# PCMCIA.net
KiCad netlist of a schematic drawn in Altium Designer
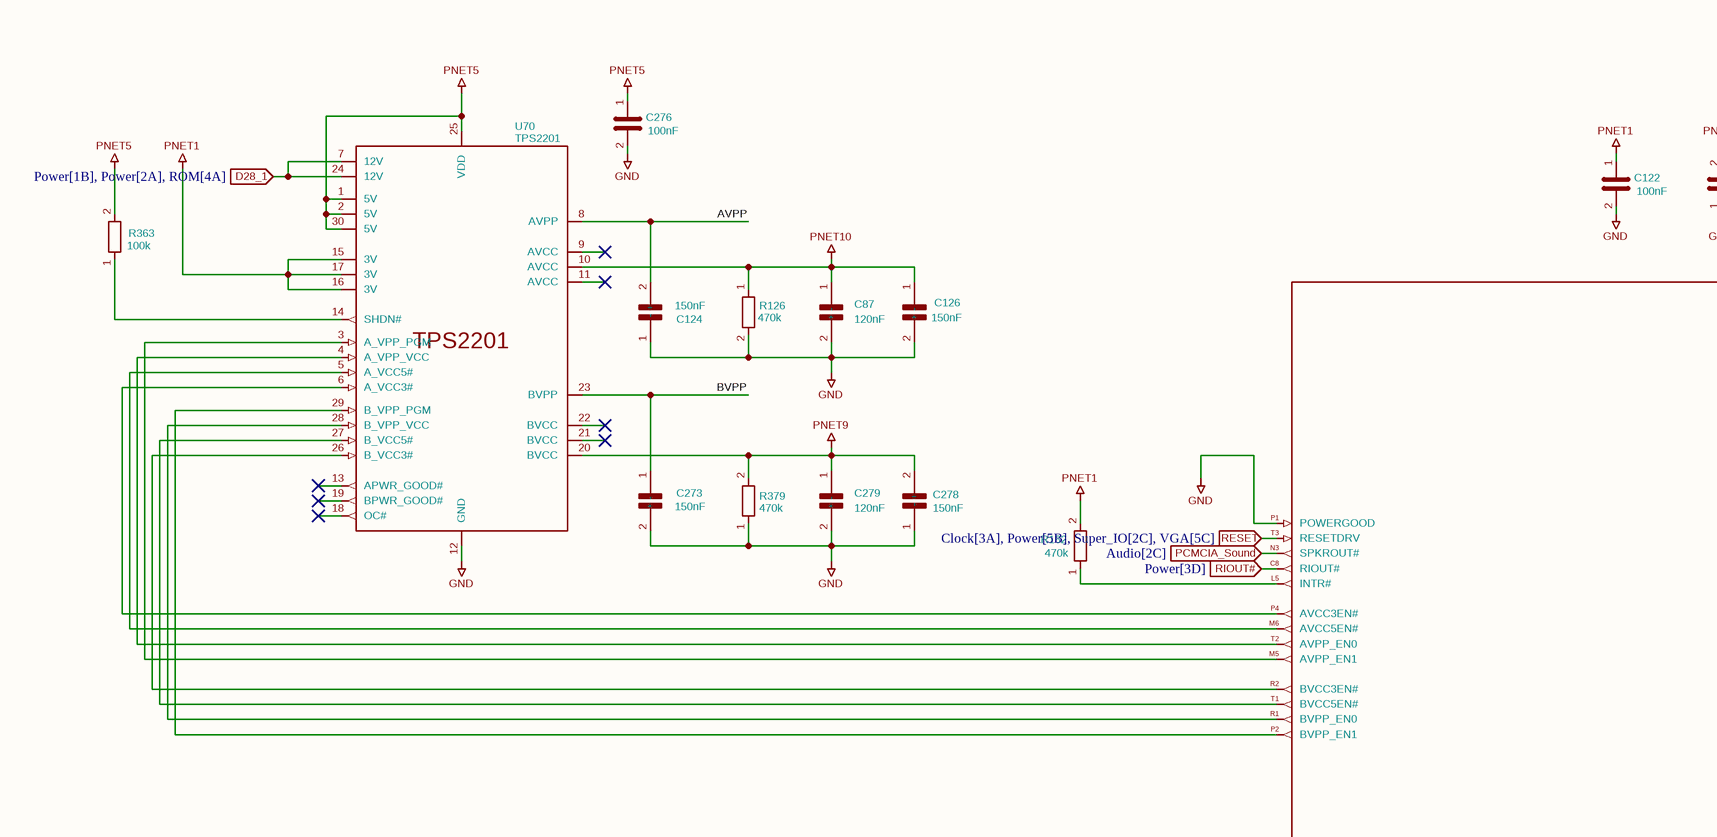
[diagram p0: PCMCIA.SchDoc, top left]
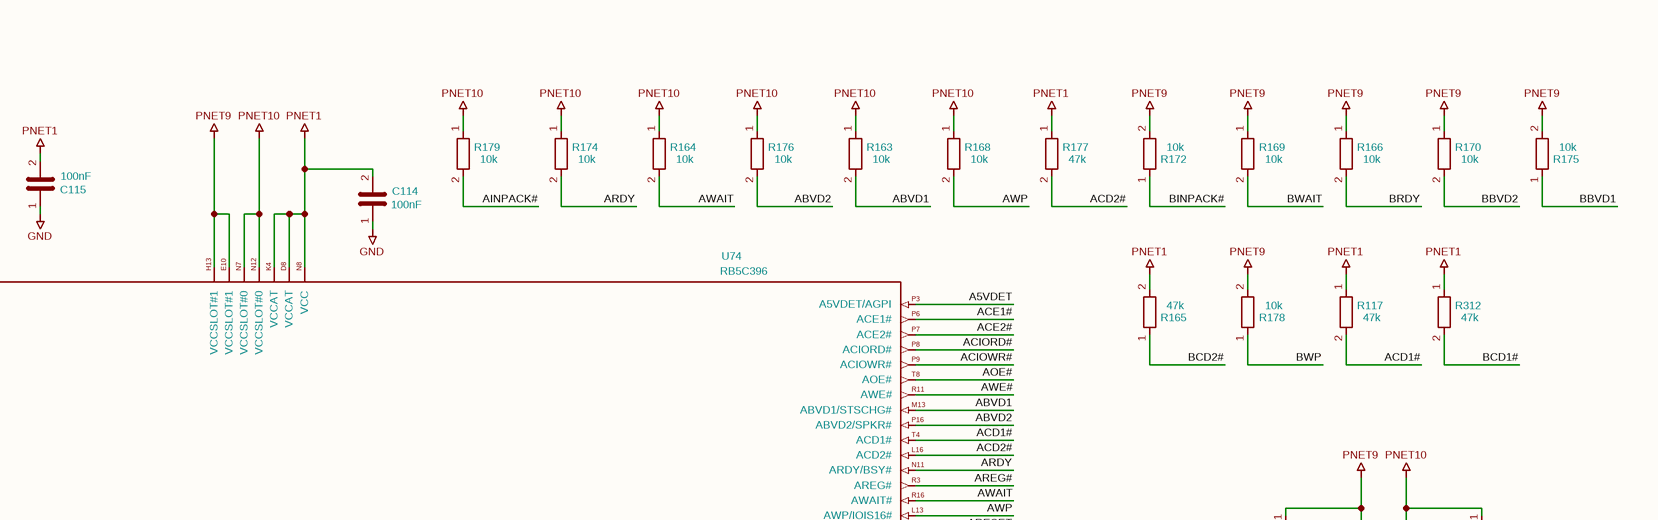
[diagram p1: PCMCIA.SchDoc, top right]
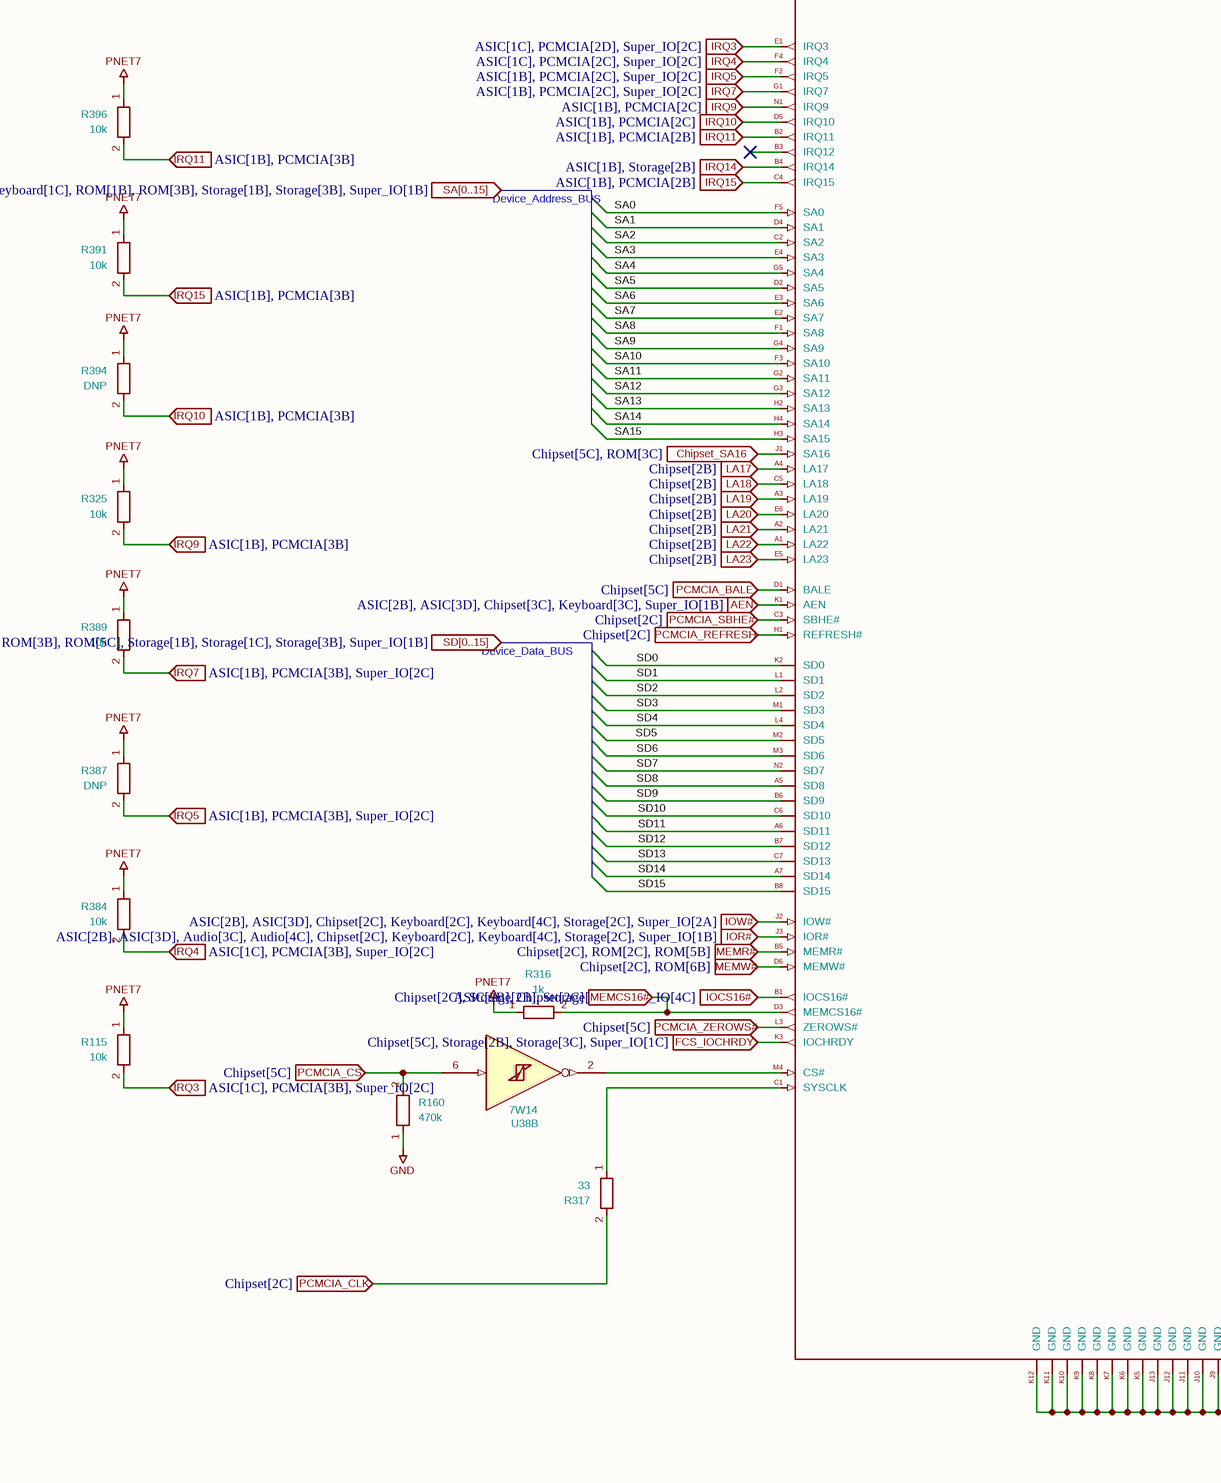
[diagram p2: PCMCIA.SchDoc, bottom left]
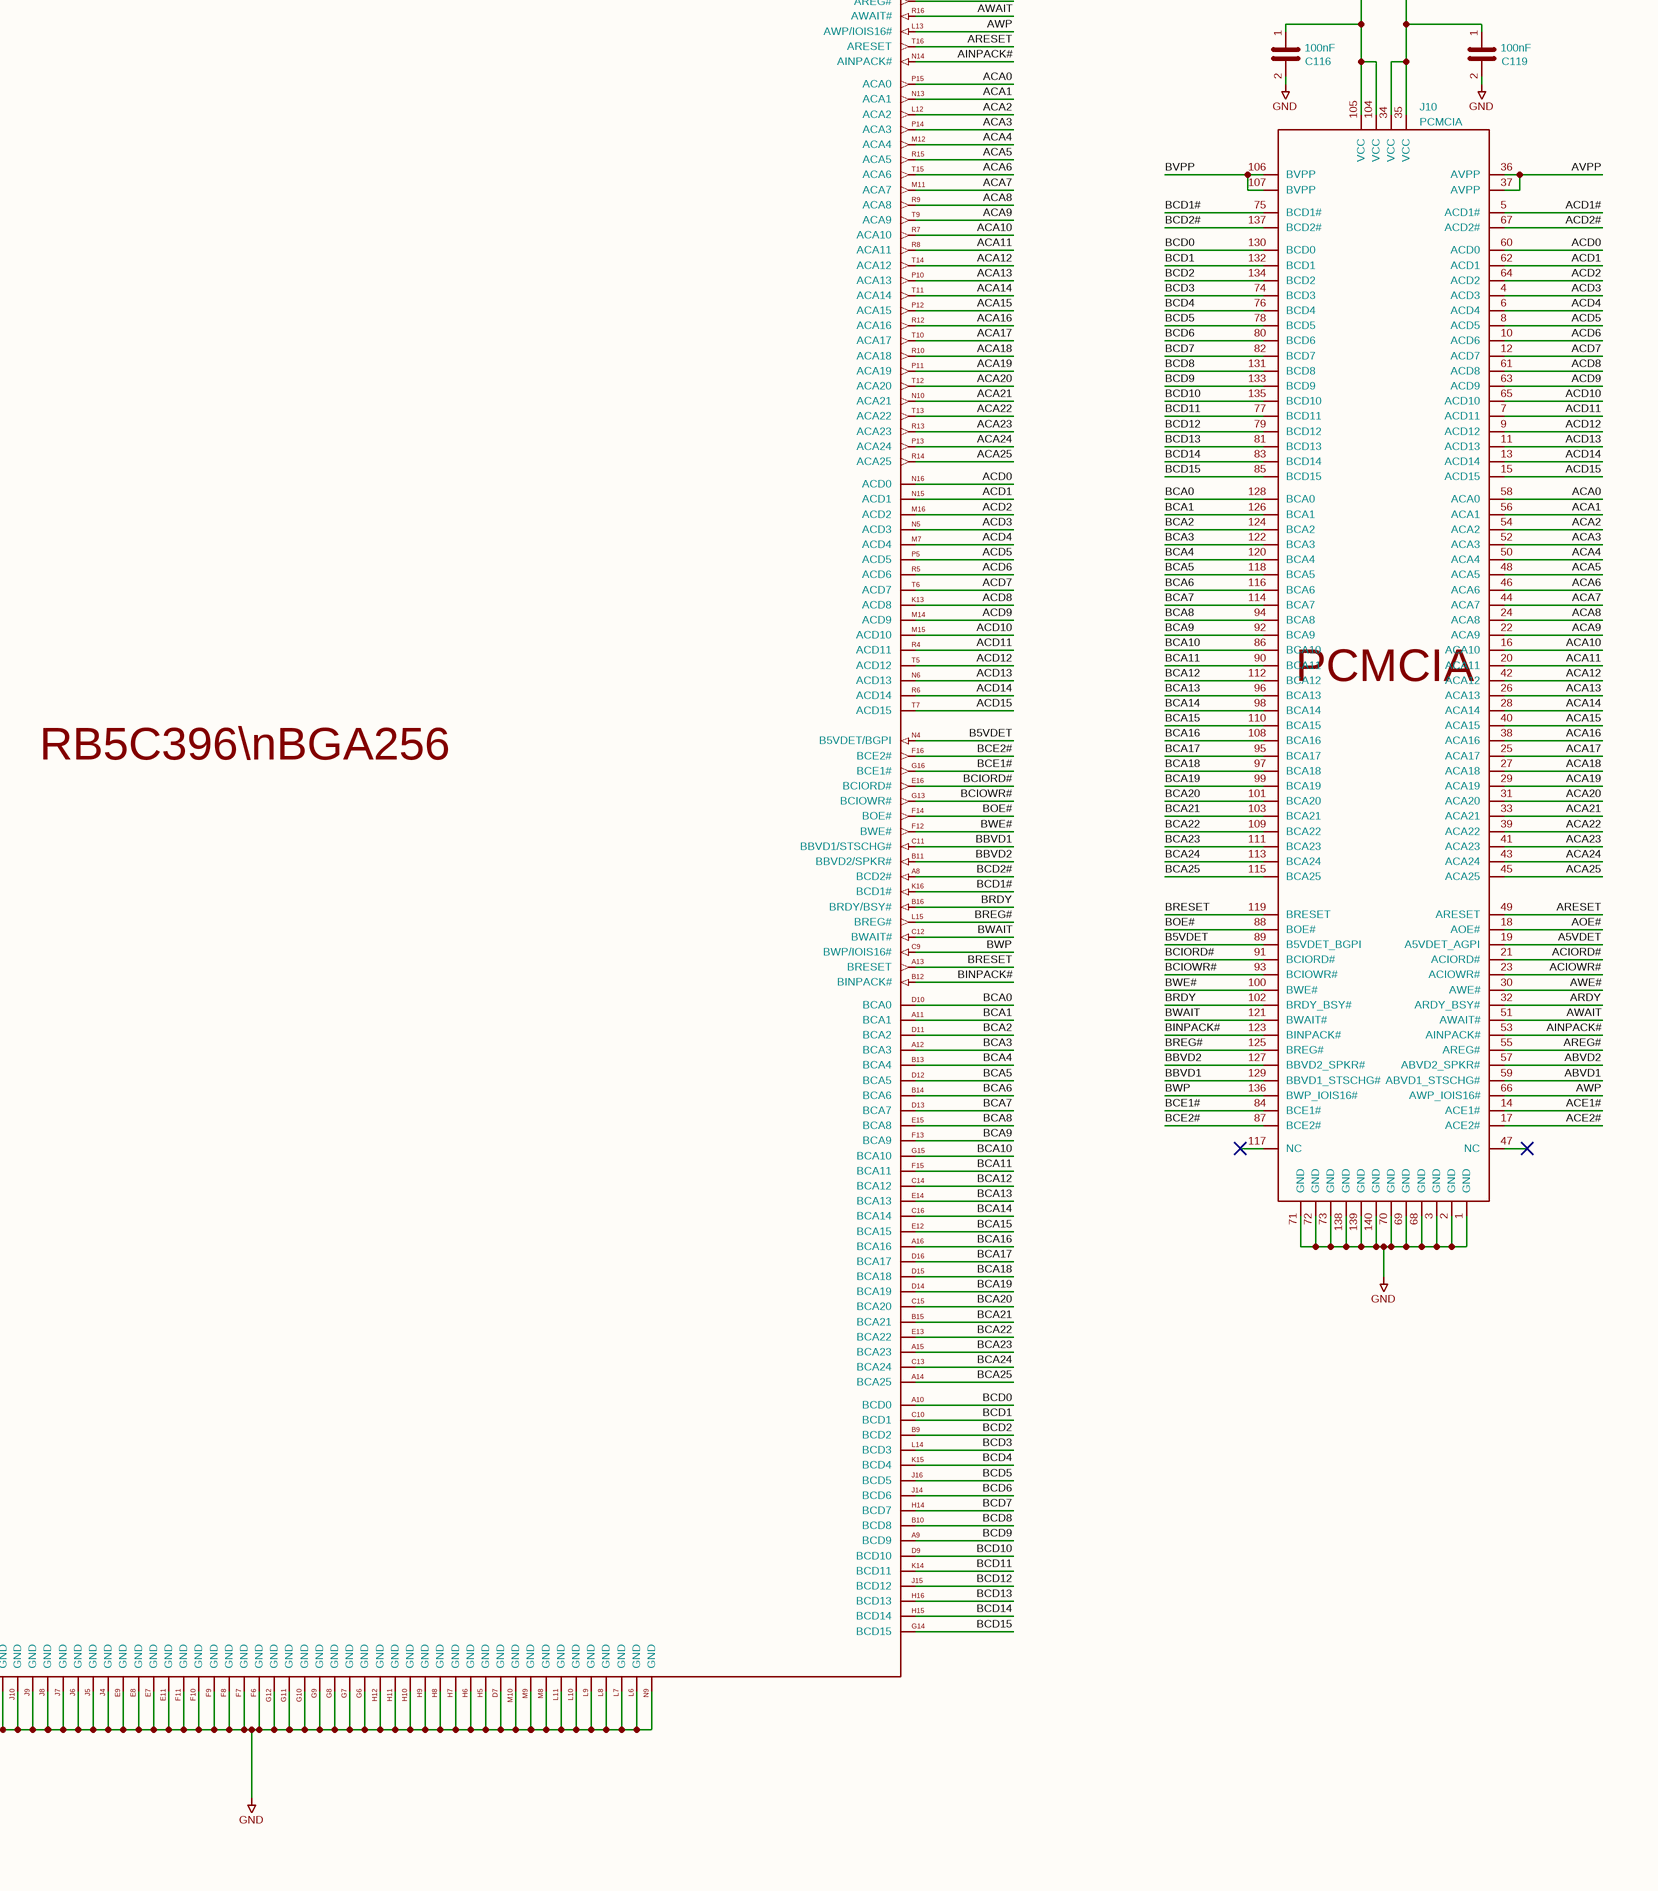
[diagram p3: PCMCIA.SchDoc, bottom right]

(export (version "E")
  (design (tool "Eeschema 10.0.6"))
  (components
    (comp (ref "C87")
      (value "120nF")
      (footprint "C_0402_1005Metric")
      (libsource (lib "PCM_Elektuur") (part "C"))
    )
    (comp (ref "C114") (value "100nF") (footprint "C_0402_1005Metric") (libsource (lib "Device") (part "C")))
    (comp (ref "C115") (value "100nF") (footprint "C_0402_1005Metric") (libsource (lib "Device") (part "C")))
    (comp (ref "C116") (value "100nF") (footprint "C_0402_1005Metric") (libsource (lib "Device") (part "C")))
    (comp (ref "C119") (value "100nF") (footprint "C_0402_1005Metric") (libsource (lib "Device") (part "C")))
    (comp (ref "C122") (value "100nF") (footprint "C_0402_1005Metric") (libsource (lib "Device") (part "C")))
    (comp (ref "C124") (value "150nF") (footprint "C_0603_1608Metric") (libsource (lib "") (part "C_1")))
    (comp (ref "C126")
      (value "150nF")
      (footprint "C_0402_1005Metric")
      (libsource (lib "PCM_Elektuur") (part "C"))
    )
    (comp (ref "C273")
      (value "150nF")
      (footprint "C_0603_1608Metric")
      (libsource (lib "PCM_Elektuur") (part "C"))
    )
    (comp (ref "C276") (value "100nF") (footprint "C_0402_1005Metric") (libsource (lib "Device") (part "C")))
    (comp (ref "C278") (value "150nF") (footprint "C_0402_1005Metric") (libsource (lib "") (part "C_1")))
    (comp (ref "C279")
      (value "120nF")
      (footprint "C_0402_1005Metric")
      (libsource (lib "PCM_Elektuur") (part "C"))
    )
    (comp (ref "J10") (value "PCMCIA") (footprint "PCMCIA") (libsource (lib "PC110") (part "PCMCIA_Conn")))
    (comp (ref "R115") (value "10k") (footprint "R_0402_1005Metric") (libsource (lib "Device") (part "R")))
    (comp (ref "R117") (value "47k") (footprint "R_0402_1005Metric") (libsource (lib "") (part "R_1")))
    (comp (ref "R126") (value "470k") (footprint "R_0402_1005Metric") (libsource (lib "") (part "R_1")))
    (comp (ref "R160") (value "470k") (footprint "R_0402_1005Metric") (libsource (lib "") (part "R_3")))
    (comp (ref "R162") (value "470k") (footprint "R_0402_1005Metric") (libsource (lib "") (part "R_3")))
    (comp (ref "R163") (value "10k") (footprint "R_0402_1005Metric") (libsource (lib "") (part "R_1")))
    (comp (ref "R164") (value "10k") (footprint "R_0402_1005Metric") (libsource (lib "") (part "R_1")))
    (comp (ref "R165") (value "47k") (footprint "R_0402_1005Metric") (libsource (lib "") (part "R_2")))
    (comp (ref "R166") (value "10k") (footprint "R_0402_1005Metric") (libsource (lib "") (part "R_1")))
    (comp (ref "R168") (value "10k") (footprint "R_0402_1005Metric") (libsource (lib "") (part "R_1")))
    (comp (ref "R169") (value "10k") (footprint "R_0402_1005Metric") (libsource (lib "") (part "R_1")))
    (comp (ref "R170") (value "10k") (footprint "R_0402_1005Metric") (libsource (lib "") (part "R_1")))
    (comp (ref "R172") (value "10k") (footprint "R_0402_1005Metric") (libsource (lib "") (part "R_2")))
    (comp (ref "R174") (value "10k") (footprint "R_0402_1005Metric") (libsource (lib "") (part "R_1")))
    (comp (ref "R175") (value "10k") (footprint "R_0402_1005Metric") (libsource (lib "") (part "R_2")))
    (comp (ref "R176") (value "10k") (footprint "R_0402_1005Metric") (libsource (lib "") (part "R_1")))
    (comp (ref "R177") (value "47k") (footprint "R_0402_1005Metric") (libsource (lib "") (part "R_1")))
    (comp (ref "R178") (value "10k") (footprint "R_0402_1005Metric") (libsource (lib "") (part "R_2")))
    (comp (ref "R179") (value "10k") (footprint "R_0402_1005Metric") (libsource (lib "") (part "R_1")))
    (comp (ref "R312") (value "47k") (footprint "R_0402_1005Metric") (libsource (lib "") (part "R_1")))
    (comp (ref "R316") (value "1k") (footprint "R_0402_1005Metric") (libsource (lib "") (part "R_2")))
    (comp (ref "R317") (value "33") (footprint "R_0402_1005Metric") (libsource (lib "") (part "R_1")))
    (comp (ref "R325") (value "10k") (footprint "R_0402_1005Metric") (libsource (lib "Device") (part "R")))
    (comp (ref "R363") (value "100k") (footprint "R_0402_1005Metric") (libsource (lib "") (part "R_2")))
    (comp (ref "R379") (value "470k") (footprint "R_0402_1005Metric") (libsource (lib "") (part "R_2")))
    (comp (ref "R384") (value "10k") (footprint "R_0402_1005Metric") (libsource (lib "Device") (part "R")))
    (comp (ref "R387") (value "DNP") (footprint "R_0402_1005Metric") (libsource (lib "Device") (part "R")))
    (comp (ref "R389") (value "10k") (footprint "R_0402_1005Metric") (libsource (lib "Device") (part "R")))
    (comp (ref "R391") (value "10k") (footprint "R_0402_1005Metric") (libsource (lib "Device") (part "R")))
    (comp (ref "R394") (value "DNP") (footprint "R_0402_1005Metric") (libsource (lib "Device") (part "R")))
    (comp (ref "R396") (value "10k") (footprint "R_0402_1005Metric") (libsource (lib "Device") (part "R")))
    (comp (ref "U38") (value "7W14") (footprint "sso-8") (libsource (lib "74xGxx") (part "74LVC3G14")))
    (comp (ref "U70")
      (value "TPS2201")
      (footprint "TSSOP-30_6.1x9.7mm_P0.65mm")
      (libsource (lib "PC110") (part "TPS2201"))
    )
    (comp (ref "U74") (value "RB5C396") (footprint "BGA-256") (libsource (lib "PC110") (part "RB5C396")))
  )
  (nets
    (net (code "1") (name "/A5VDET") (class "Default")
      (node (ref "J10") (pin "19") (pinfunction "A5VDET_AGPI_19") (pintype "bidirectional"))
      (node (ref "U74") (pin "P3") (pinfunction "A5VDET/AGPI_P3") (pintype "input"))
    )
    (net (code "2") (name "/ABVD1") (class "Default")
      (node (ref "J10") (pin "59") (pinfunction "ABVD1_STSCHG#_59") (pintype "bidirectional"))
      (node (ref "R163") (pin "2") (pinfunction "2_2") (pintype "passive"))
      (node (ref "U74") (pin "M13") (pinfunction "ABVD1/STSCHG#_M13") (pintype "input"))
    )
    (net (code "3") (name "/ABVD2") (class "Default")
      (node (ref "J10") (pin "57") (pinfunction "ABVD2_SPKR#_57") (pintype "bidirectional"))
      (node (ref "R176") (pin "2") (pinfunction "2_2") (pintype "passive"))
      (node (ref "U74") (pin "P16") (pinfunction "ABVD2/SPKR#_P16") (pintype "input"))
    )
    (net (code "4") (name "/ACA0") (class "Default")
      (node (ref "J10") (pin "58") (pinfunction "ACA0_58") (pintype "bidirectional"))
      (node (ref "U74") (pin "P15") (pinfunction "ACA0_P15") (pintype "output"))
    )
    (net (code "5") (name "/ACA1") (class "Default")
      (node (ref "J10") (pin "56") (pinfunction "ACA1_56") (pintype "bidirectional"))
      (node (ref "U74") (pin "N13") (pinfunction "ACA1_N13") (pintype "output"))
    )
    (net (code "6") (name "/ACA2") (class "Default")
      (node (ref "J10") (pin "54") (pinfunction "ACA2_54") (pintype "bidirectional"))
      (node (ref "U74") (pin "L12") (pinfunction "ACA2_L12") (pintype "output"))
    )
    (net (code "7") (name "/ACA3") (class "Default")
      (node (ref "J10") (pin "52") (pinfunction "ACA3_52") (pintype "bidirectional"))
      (node (ref "U74") (pin "P14") (pinfunction "ACA3_P14") (pintype "output"))
    )
    (net (code "8") (name "/ACA4") (class "Default")
      (node (ref "J10") (pin "50") (pinfunction "ACA4_50") (pintype "bidirectional"))
      (node (ref "U74") (pin "M12") (pinfunction "ACA4_M12") (pintype "output"))
    )
    (net (code "9") (name "/ACA5") (class "Default")
      (node (ref "J10") (pin "48") (pinfunction "ACA5_48") (pintype "bidirectional"))
      (node (ref "U74") (pin "R15") (pinfunction "ACA5_R15") (pintype "output"))
    )
    (net (code "10") (name "/ACA6") (class "Default")
      (node (ref "J10") (pin "46") (pinfunction "ACA6_46") (pintype "bidirectional"))
      (node (ref "U74") (pin "T15") (pinfunction "ACA6_T15") (pintype "output"))
    )
    (net (code "11") (name "/ACA7") (class "Default")
      (node (ref "J10") (pin "44") (pinfunction "ACA7_44") (pintype "bidirectional"))
      (node (ref "U74") (pin "M11") (pinfunction "ACA7_M11") (pintype "output"))
    )
    (net (code "12") (name "/ACA8") (class "Default")
      (node (ref "J10") (pin "24") (pinfunction "ACA8_24") (pintype "bidirectional"))
      (node (ref "U74") (pin "R9") (pinfunction "ACA8_R9") (pintype "output"))
    )
    (net (code "13") (name "/ACA9") (class "Default")
      (node (ref "J10") (pin "22") (pinfunction "ACA9_22") (pintype "bidirectional"))
      (node (ref "U74") (pin "T9") (pinfunction "ACA9_T9") (pintype "output"))
    )
    (net (code "14") (name "/ACA10") (class "Default")
      (node (ref "J10") (pin "16") (pinfunction "ACA10_16") (pintype "bidirectional"))
      (node (ref "U74") (pin "R7") (pinfunction "ACA10_R7") (pintype "output"))
    )
    (net (code "15") (name "/ACA11") (class "Default")
      (node (ref "J10") (pin "20") (pinfunction "ACA11_20") (pintype "bidirectional"))
      (node (ref "U74") (pin "R8") (pinfunction "ACA11_R8") (pintype "output"))
    )
    (net (code "16") (name "/ACA12") (class "Default")
      (node (ref "J10") (pin "42") (pinfunction "ACA12_42") (pintype "bidirectional"))
      (node (ref "U74") (pin "T14") (pinfunction "ACA12_T14") (pintype "output"))
    )
    (net (code "17") (name "/ACA13") (class "Default")
      (node (ref "J10") (pin "26") (pinfunction "ACA13_26") (pintype "bidirectional"))
      (node (ref "U74") (pin "P10") (pinfunction "ACA13_P10") (pintype "output"))
    )
    (net (code "18") (name "/ACA14") (class "Default")
      (node (ref "J10") (pin "28") (pinfunction "ACA14_28") (pintype "bidirectional"))
      (node (ref "U74") (pin "T11") (pinfunction "ACA14_T11") (pintype "output"))
    )
    (net (code "19") (name "/ACA15") (class "Default")
      (node (ref "J10") (pin "40") (pinfunction "ACA15_40") (pintype "bidirectional"))
      (node (ref "U74") (pin "P12") (pinfunction "ACA15_P12") (pintype "output"))
    )
    (net (code "20") (name "/ACA16") (class "Default")
      (node (ref "J10") (pin "38") (pinfunction "ACA16_38") (pintype "bidirectional"))
      (node (ref "U74") (pin "R12") (pinfunction "ACA16_R12") (pintype "output"))
    )
    (net (code "21") (name "/ACA17") (class "Default")
      (node (ref "J10") (pin "25") (pinfunction "ACA17_25") (pintype "bidirectional"))
      (node (ref "U74") (pin "T10") (pinfunction "ACA17_T10") (pintype "output"))
    )
    (net (code "22") (name "/ACA18") (class "Default")
      (node (ref "J10") (pin "27") (pinfunction "ACA18_27") (pintype "bidirectional"))
      (node (ref "U74") (pin "R10") (pinfunction "ACA18_R10") (pintype "output"))
    )
    (net (code "23") (name "/ACA19") (class "Default")
      (node (ref "J10") (pin "29") (pinfunction "ACA19_29") (pintype "bidirectional"))
      (node (ref "U74") (pin "P11") (pinfunction "ACA19_P11") (pintype "output"))
    )
    (net (code "24") (name "/ACA20") (class "Default")
      (node (ref "J10") (pin "31") (pinfunction "ACA20_31") (pintype "bidirectional"))
      (node (ref "U74") (pin "T12") (pinfunction "ACA20_T12") (pintype "output"))
    )
    (net (code "25") (name "/ACA21") (class "Default")
      (node (ref "J10") (pin "33") (pinfunction "ACA21_33") (pintype "bidirectional"))
      (node (ref "U74") (pin "N10") (pinfunction "ACA21_N10") (pintype "output"))
    )
    (net (code "26") (name "/ACA22") (class "Default")
      (node (ref "J10") (pin "39") (pinfunction "ACA22_39") (pintype "bidirectional"))
      (node (ref "U74") (pin "T13") (pinfunction "ACA22_T13") (pintype "output"))
    )
    (net (code "27") (name "/ACA23") (class "Default")
      (node (ref "J10") (pin "41") (pinfunction "ACA23_41") (pintype "bidirectional"))
      (node (ref "U74") (pin "R13") (pinfunction "ACA23_R13") (pintype "output"))
    )
    (net (code "28") (name "/ACA24") (class "Default")
      (node (ref "J10") (pin "43") (pinfunction "ACA24_43") (pintype "bidirectional"))
      (node (ref "U74") (pin "P13") (pinfunction "ACA24_P13") (pintype "output"))
    )
    (net (code "29") (name "/ACA25") (class "Default")
      (node (ref "J10") (pin "45") (pinfunction "ACA25_45") (pintype "bidirectional"))
      (node (ref "U74") (pin "R14") (pinfunction "ACA25_R14") (pintype "output"))
    )
    (net (code "30") (name "/ACD0") (class "Default")
      (node (ref "J10") (pin "60") (pinfunction "ACD0_60") (pintype "bidirectional"))
      (node (ref "U74") (pin "N16") (pinfunction "ACD0_N16") (pintype "bidirectional"))
    )
    (net (code "31") (name "/ACD1") (class "Default")
      (node (ref "J10") (pin "62") (pinfunction "ACD1_62") (pintype "bidirectional"))
      (node (ref "U74") (pin "N15") (pinfunction "ACD1_N15") (pintype "bidirectional"))
    )
    (net (code "32") (name "/ACD1#") (class "Default")
      (node (ref "J10") (pin "5") (pinfunction "ACD1#_5") (pintype "bidirectional"))
      (node (ref "R117") (pin "2") (pinfunction "2_2") (pintype "passive"))
      (node (ref "U74") (pin "T4") (pinfunction "ACD1#_T4") (pintype "input"))
    )
    (net (code "33") (name "/ACD2") (class "Default")
      (node (ref "J10") (pin "64") (pinfunction "ACD2_64") (pintype "bidirectional"))
      (node (ref "U74") (pin "M16") (pinfunction "ACD2_M16") (pintype "bidirectional"))
    )
    (net (code "34") (name "/ACD2#") (class "Default")
      (node (ref "J10") (pin "67") (pinfunction "ACD2#_67") (pintype "bidirectional"))
      (node (ref "R177") (pin "2") (pinfunction "2_2") (pintype "passive"))
      (node (ref "U74") (pin "L16") (pinfunction "ACD2#_L16") (pintype "input"))
    )
    (net (code "35") (name "/ACD3") (class "Default")
      (node (ref "J10") (pin "4") (pinfunction "ACD3_4") (pintype "bidirectional"))
      (node (ref "U74") (pin "N5") (pinfunction "ACD3_N5") (pintype "bidirectional"))
    )
    (net (code "36") (name "/ACD4") (class "Default")
      (node (ref "J10") (pin "6") (pinfunction "ACD4_6") (pintype "bidirectional"))
      (node (ref "U74") (pin "M7") (pinfunction "ACD4_M7") (pintype "bidirectional"))
    )
    (net (code "37") (name "/ACD5") (class "Default")
      (node (ref "J10") (pin "8") (pinfunction "ACD5_8") (pintype "bidirectional"))
      (node (ref "U74") (pin "P5") (pinfunction "ACD5_P5") (pintype "bidirectional"))
    )
    (net (code "38") (name "/ACD6") (class "Default")
      (node (ref "J10") (pin "10") (pinfunction "ACD6_10") (pintype "bidirectional"))
      (node (ref "U74") (pin "R5") (pinfunction "ACD6_R5") (pintype "bidirectional"))
    )
    (net (code "39") (name "/ACD7") (class "Default")
      (node (ref "J10") (pin "12") (pinfunction "ACD7_12") (pintype "bidirectional"))
      (node (ref "U74") (pin "T6") (pinfunction "ACD7_T6") (pintype "bidirectional"))
    )
    (net (code "40") (name "/ACD8") (class "Default")
      (node (ref "J10") (pin "61") (pinfunction "ACD8_61") (pintype "bidirectional"))
      (node (ref "U74") (pin "K13") (pinfunction "ACD8_K13") (pintype "bidirectional"))
    )
    (net (code "41") (name "/ACD9") (class "Default")
      (node (ref "J10") (pin "63") (pinfunction "ACD9_63") (pintype "bidirectional"))
      (node (ref "U74") (pin "M14") (pinfunction "ACD9_M14") (pintype "bidirectional"))
    )
    (net (code "42") (name "/ACD10") (class "Default")
      (node (ref "J10") (pin "65") (pinfunction "ACD10_65") (pintype "bidirectional"))
      (node (ref "U74") (pin "M15") (pinfunction "ACD10_M15") (pintype "bidirectional"))
    )
    (net (code "43") (name "/ACD11") (class "Default")
      (node (ref "J10") (pin "7") (pinfunction "ACD11_7") (pintype "bidirectional"))
      (node (ref "U74") (pin "R4") (pinfunction "ACD11_R4") (pintype "bidirectional"))
    )
    (net (code "44") (name "/ACD12") (class "Default")
      (node (ref "J10") (pin "9") (pinfunction "ACD12_9") (pintype "bidirectional"))
      (node (ref "U74") (pin "T5") (pinfunction "ACD12_T5") (pintype "bidirectional"))
    )
    (net (code "45") (name "/ACD13") (class "Default")
      (node (ref "J10") (pin "11") (pinfunction "ACD13_11") (pintype "bidirectional"))
      (node (ref "U74") (pin "N6") (pinfunction "ACD13_N6") (pintype "bidirectional"))
    )
    (net (code "46") (name "/ACD14") (class "Default")
      (node (ref "J10") (pin "13") (pinfunction "ACD14_13") (pintype "bidirectional"))
      (node (ref "U74") (pin "R6") (pinfunction "ACD14_R6") (pintype "bidirectional"))
    )
    (net (code "47") (name "/ACD15") (class "Default")
      (node (ref "J10") (pin "15") (pinfunction "ACD15_15") (pintype "bidirectional"))
      (node (ref "U74") (pin "T7") (pinfunction "ACD15_T7") (pintype "bidirectional"))
    )
    (net (code "48") (name "/ACE1#") (class "Default")
      (node (ref "J10") (pin "14") (pinfunction "ACE1#_14") (pintype "bidirectional"))
      (node (ref "U74") (pin "P6") (pinfunction "ACE1#_P6") (pintype "output"))
    )
    (net (code "49") (name "/ACE2#") (class "Default")
      (node (ref "J10") (pin "17") (pinfunction "ACE2#_17") (pintype "bidirectional"))
      (node (ref "U74") (pin "P7") (pinfunction "ACE2#_P7") (pintype "output"))
    )
    (net (code "50") (name "/ACIORD#") (class "Default")
      (node (ref "J10") (pin "21") (pinfunction "ACIORD#_21") (pintype "bidirectional"))
      (node (ref "U74") (pin "P8") (pinfunction "ACIORD#_P8") (pintype "output"))
    )
    (net (code "51") (name "/ACIOWR#") (class "Default")
      (node (ref "J10") (pin "23") (pinfunction "ACIOWR#_23") (pintype "bidirectional"))
      (node (ref "U74") (pin "P9") (pinfunction "ACIOWR#_P9") (pintype "output"))
    )
    (net (code "52") (name "/AEN") (class "Default")
      (node (ref "U74") (pin "K1") (pinfunction "AEN_K1") (pintype "input"))
    )
    (net (code "53") (name "/AINPACK#") (class "Default")
      (node (ref "J10") (pin "53") (pinfunction "AINPACK#_53") (pintype "bidirectional"))
      (node (ref "R179") (pin "2") (pinfunction "2_2") (pintype "passive"))
      (node (ref "U74") (pin "N14") (pinfunction "AINPACK#_N14") (pintype "input"))
    )
    (net (code "54") (name "/AOE#") (class "Default")
      (node (ref "J10") (pin "18") (pinfunction "AOE#_18") (pintype "bidirectional"))
      (node (ref "U74") (pin "T8") (pinfunction "AOE#_T8") (pintype "output"))
    )
    (net (code "55") (name "/ARDY") (class "Default")
      (node (ref "J10") (pin "32") (pinfunction "ARDY_BSY#_32") (pintype "bidirectional"))
      (node (ref "R174") (pin "2") (pinfunction "2_2") (pintype "passive"))
      (node (ref "U74") (pin "N11") (pinfunction "ARDY/BSY#_N11") (pintype "input"))
    )
    (net (code "56") (name "/AREG#") (class "Default")
      (node (ref "J10") (pin "55") (pinfunction "AREG#_55") (pintype "bidirectional"))
      (node (ref "U74") (pin "R3") (pinfunction "AREG#_R3") (pintype "output"))
    )
    (net (code "57") (name "/ARESET") (class "Default")
      (node (ref "J10") (pin "49") (pinfunction "ARESET_49") (pintype "bidirectional"))
      (node (ref "U74") (pin "T16") (pinfunction "ARESET_T16") (pintype "output"))
    )
    (net (code "58") (name "/AVPP") (class "Default")
      (node (ref "C124") (pin "2") (pinfunction "-_2") (pintype "passive"))
      (node (ref "J10") (pin "36") (pinfunction "AVPP_36") (pintype "power_in"))
      (node (ref "J10") (pin "37") (pinfunction "AVPP_37") (pintype "power_in"))
      (node (ref "U70") (pin "8") (pinfunction "AVPP_8") (pintype "power_in"))
    )
    (net (code "59") (name "/AWAIT") (class "Default")
      (node (ref "J10") (pin "51") (pinfunction "AWAIT#_51") (pintype "bidirectional"))
      (node (ref "R164") (pin "2") (pinfunction "2_2") (pintype "passive"))
      (node (ref "U74") (pin "R16") (pinfunction "AWAIT#_R16") (pintype "input"))
    )
    (net (code "60") (name "/AWE#") (class "Default")
      (node (ref "J10") (pin "30") (pinfunction "AWE#_30") (pintype "bidirectional"))
      (node (ref "U74") (pin "R11") (pinfunction "AWE#_R11") (pintype "output"))
    )
    (net (code "61") (name "/AWP") (class "Default")
      (node (ref "J10") (pin "66") (pinfunction "AWP_IOIS16#_66") (pintype "bidirectional"))
      (node (ref "R168") (pin "2") (pinfunction "2_2") (pintype "passive"))
      (node (ref "U74") (pin "L13") (pinfunction "AWP/IOIS16#_L13") (pintype "input"))
    )
    (net (code "62") (name "/B5VDET") (class "Default")
      (node (ref "J10") (pin "89") (pinfunction "B5VDET_BGPI_89") (pintype "bidirectional"))
      (node (ref "U74") (pin "N4") (pinfunction "B5VDET/BGPI_N4") (pintype "input"))
    )
    (net (code "63") (name "/BBVD1") (class "Default")
      (node (ref "J10") (pin "129") (pinfunction "BBVD1_STSCHG#_129") (pintype "bidirectional"))
      (node (ref "R175") (pin "1") (pinfunction "1_1") (pintype "passive"))
      (node (ref "U74") (pin "C11") (pinfunction "BBVD1/STSCHG#_C11") (pintype "input"))
    )
    (net (code "64") (name "/BBVD2") (class "Default")
      (node (ref "J10") (pin "127") (pinfunction "BBVD2_SPKR#_127") (pintype "bidirectional"))
      (node (ref "R170") (pin "2") (pinfunction "2_2") (pintype "passive"))
      (node (ref "U74") (pin "B11") (pinfunction "BBVD2/SPKR#_B11") (pintype "input"))
    )
    (net (code "65") (name "/BCA0") (class "Default")
      (node (ref "J10") (pin "128") (pinfunction "BCA0_128") (pintype "bidirectional"))
      (node (ref "U74") (pin "D10") (pinfunction "BCA0_D10") (pintype "bidirectional"))
    )
    (net (code "66") (name "/BCA1") (class "Default")
      (node (ref "J10") (pin "126") (pinfunction "BCA1_126") (pintype "bidirectional"))
      (node (ref "U74") (pin "A11") (pinfunction "BCA1_A11") (pintype "bidirectional"))
    )
    (net (code "67") (name "/BCA2") (class "Default")
      (node (ref "J10") (pin "124") (pinfunction "BCA2_124") (pintype "bidirectional"))
      (node (ref "U74") (pin "D11") (pinfunction "BCA2_D11") (pintype "bidirectional"))
    )
    (net (code "68") (name "/BCA3") (class "Default")
      (node (ref "J10") (pin "122") (pinfunction "BCA3_122") (pintype "bidirectional"))
      (node (ref "U74") (pin "A12") (pinfunction "BCA3_A12") (pintype "bidirectional"))
    )
    (net (code "69") (name "/BCA4") (class "Default")
      (node (ref "J10") (pin "120") (pinfunction "BCA4_120") (pintype "bidirectional"))
      (node (ref "U74") (pin "B13") (pinfunction "BCA4_B13") (pintype "bidirectional"))
    )
    (net (code "70") (name "/BCA5") (class "Default")
      (node (ref "J10") (pin "118") (pinfunction "BCA5_118") (pintype "bidirectional"))
      (node (ref "U74") (pin "D12") (pinfunction "BCA5_D12") (pintype "bidirectional"))
    )
    (net (code "71") (name "/BCA6") (class "Default")
      (node (ref "J10") (pin "116") (pinfunction "BCA6_116") (pintype "bidirectional"))
      (node (ref "U74") (pin "B14") (pinfunction "BCA6_B14") (pintype "bidirectional"))
    )
    (net (code "72") (name "/BCA7") (class "Default")
      (node (ref "J10") (pin "114") (pinfunction "BCA7_114") (pintype "bidirectional"))
      (node (ref "U74") (pin "D13") (pinfunction "BCA7_D13") (pintype "bidirectional"))
    )
    (net (code "73") (name "/BCA8") (class "Default")
      (node (ref "J10") (pin "94") (pinfunction "BCA8_94") (pintype "bidirectional"))
      (node (ref "U74") (pin "E15") (pinfunction "BCA8_E15") (pintype "bidirectional"))
    )
    (net (code "74") (name "/BCA9") (class "Default")
      (node (ref "J10") (pin "92") (pinfunction "BCA9_92") (pintype "bidirectional"))
      (node (ref "U74") (pin "F13") (pinfunction "BCA9_F13") (pintype "bidirectional"))
    )
    (net (code "75") (name "/BCA10") (class "Default")
      (node (ref "J10") (pin "86") (pinfunction "BCA10_86") (pintype "bidirectional"))
      (node (ref "U74") (pin "G15") (pinfunction "BCA10_G15") (pintype "bidirectional"))
    )
    (net (code "76") (name "/BCA11") (class "Default")
      (node (ref "J10") (pin "90") (pinfunction "BCA11_90") (pintype "bidirectional"))
      (node (ref "U74") (pin "F15") (pinfunction "BCA11_F15") (pintype "bidirectional"))
    )
    (net (code "77") (name "/BCA12") (class "Default")
      (node (ref "J10") (pin "112") (pinfunction "BCA12_112") (pintype "bidirectional"))
      (node (ref "U74") (pin "C14") (pinfunction "BCA12_C14") (pintype "bidirectional"))
    )
    (net (code "78") (name "/BCA13") (class "Default")
      (node (ref "J10") (pin "96") (pinfunction "BCA13_96") (pintype "bidirectional"))
      (node (ref "U74") (pin "E14") (pinfunction "BCA13_E14") (pintype "bidirectional"))
    )
    (net (code "79") (name "/BCA14") (class "Default")
      (node (ref "J10") (pin "98") (pinfunction "BCA14_98") (pintype "bidirectional"))
      (node (ref "U74") (pin "C16") (pinfunction "BCA14_C16") (pintype "bidirectional"))
    )
    (net (code "80") (name "/BCA15") (class "Default")
      (node (ref "J10") (pin "110") (pinfunction "BCA15_110") (pintype "bidirectional"))
      (node (ref "U74") (pin "E12") (pinfunction "BCA15_E12") (pintype "bidirectional"))
    )
    (net (code "81") (name "/BCA16") (class "Default")
      (node (ref "J10") (pin "108") (pinfunction "BCA16_108") (pintype "bidirectional"))
      (node (ref "U74") (pin "A16") (pinfunction "BCA16_A16") (pintype "bidirectional"))
    )
    (net (code "82") (name "/BCA17") (class "Default")
      (node (ref "J10") (pin "95") (pinfunction "BCA17_95") (pintype "bidirectional"))
      (node (ref "U74") (pin "D16") (pinfunction "BCA17_D16") (pintype "bidirectional"))
    )
    (net (code "83") (name "/BCA18") (class "Default")
      (node (ref "J10") (pin "97") (pinfunction "BCA18_97") (pintype "bidirectional"))
      (node (ref "U74") (pin "D15") (pinfunction "BCA18_D15") (pintype "bidirectional"))
    )
    (net (code "84") (name "/BCA19") (class "Default")
      (node (ref "J10") (pin "99") (pinfunction "BCA19_99") (pintype "bidirectional"))
      (node (ref "U74") (pin "D14") (pinfunction "BCA19_D14") (pintype "bidirectional"))
    )
    (net (code "85") (name "/BCA20") (class "Default")
      (node (ref "J10") (pin "101") (pinfunction "BCA20_101") (pintype "bidirectional"))
      (node (ref "U74") (pin "C15") (pinfunction "BCA20_C15") (pintype "bidirectional"))
    )
    (net (code "86") (name "/BCA21") (class "Default")
      (node (ref "J10") (pin "103") (pinfunction "BCA21_103") (pintype "bidirectional"))
      (node (ref "U74") (pin "B15") (pinfunction "BCA21_B15") (pintype "bidirectional"))
    )
    (net (code "87") (name "/BCA22") (class "Default")
      (node (ref "J10") (pin "109") (pinfunction "BCA22_109") (pintype "bidirectional"))
      (node (ref "U74") (pin "E13") (pinfunction "BCA22_E13") (pintype "bidirectional"))
    )
    (net (code "88") (name "/BCA23") (class "Default")
      (node (ref "J10") (pin "111") (pinfunction "BCA23_111") (pintype "bidirectional"))
      (node (ref "U74") (pin "A15") (pinfunction "BCA23_A15") (pintype "bidirectional"))
    )
    (net (code "89") (name "/BCA24") (class "Default")
      (node (ref "J10") (pin "113") (pinfunction "BCA24_113") (pintype "bidirectional"))
      (node (ref "U74") (pin "C13") (pinfunction "BCA24_C13") (pintype "bidirectional"))
    )
    (net (code "90") (name "/BCA25") (class "Default")
      (node (ref "J10") (pin "115") (pinfunction "BCA25_115") (pintype "bidirectional"))
      (node (ref "U74") (pin "A14") (pinfunction "BCA25_A14") (pintype "bidirectional"))
    )
    (net (code "91") (name "/BCD0") (class "Default")
      (node (ref "J10") (pin "130") (pinfunction "BCD0_130") (pintype "bidirectional"))
      (node (ref "U74") (pin "A10") (pinfunction "BCD0_A10") (pintype "bidirectional"))
    )
    (net (code "92") (name "/BCD1") (class "Default")
      (node (ref "J10") (pin "132") (pinfunction "BCD1_132") (pintype "bidirectional"))
      (node (ref "U74") (pin "C10") (pinfunction "BCD1_C10") (pintype "bidirectional"))
    )
    (net (code "93") (name "/BCD1#") (class "Default")
      (node (ref "J10") (pin "75") (pinfunction "BCD1#_75") (pintype "bidirectional"))
      (node (ref "R312") (pin "2") (pinfunction "2_2") (pintype "passive"))
      (node (ref "U74") (pin "K16") (pinfunction "BCD1#_K16") (pintype "input"))
    )
    (net (code "94") (name "/BCD2") (class "Default")
      (node (ref "J10") (pin "134") (pinfunction "BCD2_134") (pintype "bidirectional"))
      (node (ref "U74") (pin "B9") (pinfunction "BCD2_B9") (pintype "bidirectional"))
    )
    (net (code "95") (name "/BCD2#") (class "Default")
      (node (ref "J10") (pin "137") (pinfunction "BCD2#_137") (pintype "bidirectional"))
      (node (ref "R165") (pin "1") (pinfunction "1_1") (pintype "passive"))
      (node (ref "U74") (pin "A8") (pinfunction "BCD2#_A8") (pintype "input"))
    )
    (net (code "96") (name "/BCD3") (class "Default")
      (node (ref "J10") (pin "74") (pinfunction "BCD3_74") (pintype "bidirectional"))
      (node (ref "U74") (pin "L14") (pinfunction "BCD3_L14") (pintype "bidirectional"))
    )
    (net (code "97") (name "/BCD4") (class "Default")
      (node (ref "J10") (pin "76") (pinfunction "BCD4_76") (pintype "bidirectional"))
      (node (ref "U74") (pin "K15") (pinfunction "BCD4_K15") (pintype "bidirectional"))
    )
    (net (code "98") (name "/BCD5") (class "Default")
      (node (ref "J10") (pin "78") (pinfunction "BCD5_78") (pintype "bidirectional"))
      (node (ref "U74") (pin "J16") (pinfunction "BCD5_J16") (pintype "bidirectional"))
    )
    (net (code "99") (name "/BCD6") (class "Default")
      (node (ref "J10") (pin "80") (pinfunction "BCD6_80") (pintype "bidirectional"))
      (node (ref "U74") (pin "J14") (pinfunction "BCD6_J14") (pintype "bidirectional"))
    )
    (net (code "100") (name "/BCD7") (class "Default")
      (node (ref "J10") (pin "82") (pinfunction "BCD7_82") (pintype "bidirectional"))
      (node (ref "U74") (pin "H14") (pinfunction "BCD7_H14") (pintype "bidirectional"))
    )
    (net (code "101") (name "/BCD8") (class "Default")
      (node (ref "J10") (pin "131") (pinfunction "BCD8_131") (pintype "bidirectional"))
      (node (ref "U74") (pin "B10") (pinfunction "BCD8_B10") (pintype "bidirectional"))
    )
    (net (code "102") (name "/BCD9") (class "Default")
      (node (ref "J10") (pin "133") (pinfunction "BCD9_133") (pintype "bidirectional"))
      (node (ref "U74") (pin "A9") (pinfunction "BCD9_A9") (pintype "bidirectional"))
    )
    (net (code "103") (name "/BCD10") (class "Default")
      (node (ref "J10") (pin "135") (pinfunction "BCD10_135") (pintype "bidirectional"))
      (node (ref "U74") (pin "D9") (pinfunction "BCD10_D9") (pintype "bidirectional"))
    )
    (net (code "104") (name "/BCD11") (class "Default")
      (node (ref "J10") (pin "77") (pinfunction "BCD11_77") (pintype "bidirectional"))
      (node (ref "U74") (pin "K14") (pinfunction "BCD11_K14") (pintype "bidirectional"))
    )
    (net (code "105") (name "/BCD12") (class "Default")
      (node (ref "J10") (pin "79") (pinfunction "BCD12_79") (pintype "bidirectional"))
      (node (ref "U74") (pin "J15") (pinfunction "BCD12_J15") (pintype "bidirectional"))
    )
    (net (code "106") (name "/BCD13") (class "Default")
      (node (ref "J10") (pin "81") (pinfunction "BCD13_81") (pintype "bidirectional"))
      (node (ref "U74") (pin "H16") (pinfunction "BCD13_H16") (pintype "bidirectional"))
    )
    (net (code "107") (name "/BCD14") (class "Default")
      (node (ref "J10") (pin "83") (pinfunction "BCD14_83") (pintype "bidirectional"))
      (node (ref "U74") (pin "H15") (pinfunction "BCD14_H15") (pintype "bidirectional"))
    )
    (net (code "108") (name "/BCD15") (class "Default")
      (node (ref "J10") (pin "85") (pinfunction "BCD15_85") (pintype "bidirectional"))
      (node (ref "U74") (pin "G14") (pinfunction "BCD15_G14") (pintype "bidirectional"))
    )
    (net (code "109") (name "/BCE1#") (class "Default")
      (node (ref "J10") (pin "84") (pinfunction "BCE1#_84") (pintype "bidirectional"))
      (node (ref "U74") (pin "G16") (pinfunction "BCE1#_G16") (pintype "output"))
    )
    (net (code "110") (name "/BCE2#") (class "Default")
      (node (ref "J10") (pin "87") (pinfunction "BCE2#_87") (pintype "bidirectional"))
      (node (ref "U74") (pin "F16") (pinfunction "BCE2#_F16") (pintype "output"))
    )
    (net (code "111") (name "/BCIORD#") (class "Default")
      (node (ref "J10") (pin "91") (pinfunction "BCIORD#_91") (pintype "bidirectional"))
      (node (ref "U74") (pin "E16") (pinfunction "BCIORD#_E16") (pintype "output"))
    )
    (net (code "112") (name "/BCIOWR#") (class "Default")
      (node (ref "J10") (pin "93") (pinfunction "BCIOWR#_93") (pintype "bidirectional"))
      (node (ref "U74") (pin "G13") (pinfunction "BCIOWR#_G13") (pintype "output"))
    )
    (net (code "113") (name "/BINPACK#") (class "Default")
      (node (ref "J10") (pin "123") (pinfunction "BINPACK#_123") (pintype "bidirectional"))
      (node (ref "R172") (pin "1") (pinfunction "1_1") (pintype "passive"))
      (node (ref "U74") (pin "B12") (pinfunction "BINPACK#_B12") (pintype "input"))
    )
    (net (code "114") (name "/BOE#") (class "Default")
      (node (ref "J10") (pin "88") (pinfunction "BOE#_88") (pintype "bidirectional"))
      (node (ref "U74") (pin "F14") (pinfunction "BOE#_F14") (pintype "output"))
    )
    (net (code "115") (name "/BRDY") (class "Default")
      (node (ref "J10") (pin "102") (pinfunction "BRDY_BSY#_102") (pintype "bidirectional"))
      (node (ref "R166") (pin "2") (pinfunction "2_2") (pintype "passive"))
      (node (ref "U74") (pin "B16") (pinfunction "BRDY/BSY#_B16") (pintype "input"))
    )
    (net (code "116") (name "/BREG#") (class "Default")
      (node (ref "J10") (pin "125") (pinfunction "BREG#_125") (pintype "bidirectional"))
      (node (ref "U74") (pin "L15") (pinfunction "BREG#_L15") (pintype "output"))
    )
    (net (code "117") (name "/BRESET") (class "Default")
      (node (ref "J10") (pin "119") (pinfunction "BRESET_119") (pintype "bidirectional"))
      (node (ref "U74") (pin "A13") (pinfunction "BRESET_A13") (pintype "output"))
    )
    (net (code "118") (name "/BVPP") (class "Default")
      (node (ref "C273") (pin "1") (pinfunction "+_1") (pintype "passive"))
      (node (ref "J10") (pin "106") (pinfunction "BVPP_106") (pintype "power_in"))
      (node (ref "J10") (pin "107") (pinfunction "BVPP_107") (pintype "power_in"))
      (node (ref "U70") (pin "23") (pinfunction "BVPP_23") (pintype "power_in"))
    )
    (net (code "119") (name "/BWAIT") (class "Default")
      (node (ref "J10") (pin "121") (pinfunction "BWAIT#_121") (pintype "bidirectional"))
      (node (ref "R169") (pin "2") (pinfunction "2_2") (pintype "passive"))
      (node (ref "U74") (pin "C12") (pinfunction "BWAIT#_C12") (pintype "input"))
    )
    (net (code "120") (name "/BWE#") (class "Default")
      (node (ref "J10") (pin "100") (pinfunction "BWE#_100") (pintype "bidirectional"))
      (node (ref "U74") (pin "F12") (pinfunction "BWE#_F12") (pintype "output"))
    )
    (net (code "121") (name "/BWP") (class "Default")
      (node (ref "J10") (pin "136") (pinfunction "BWP_IOIS16#_136") (pintype "bidirectional"))
      (node (ref "R178") (pin "1") (pinfunction "1_1") (pintype "passive"))
      (node (ref "U74") (pin "C9") (pinfunction "BWP/IOIS16#_C9") (pintype "input"))
    )
    (net (code "122") (name "/Chipset_SA16") (class "Default")
      (node (ref "U74") (pin "J1") (pinfunction "SA16_J1") (pintype "input"))
    )
    (net (code "123") (name "/D28_1") (class "Default")
      (node (ref "U70") (pin "24") (pinfunction "12V_24") (pintype "power_in"))
      (node (ref "U70") (pin "7") (pinfunction "12V_7") (pintype "power_in"))
    )
    (net (code "124") (name "/FCS_IOCHRDY") (class "Default")
      (node (ref "U74") (pin "K3") (pinfunction "IOCHRDY_K3") (pintype "output"))
    )
    (net (code "125") (name "/IOCS16#") (class "Default")
      (node (ref "U74") (pin "B1") (pinfunction "IOCS16#_B1") (pintype "output"))
    )
    (net (code "126") (name "/IOR#") (class "Default")
      (node (ref "U74") (pin "J3") (pinfunction "IOR#_J3") (pintype "input"))
    )
    (net (code "127") (name "/IOW#") (class "Default")
      (node (ref "U74") (pin "J2") (pinfunction "IOW#_J2") (pintype "input"))
    )
    (net (code "128") (name "/IRQ3") (class "Default")
      (node (ref "R115") (pin "2") (pinfunction "2_2") (pintype "passive"))
      (node (ref "U74") (pin "E1") (pinfunction "IRQ3_E1") (pintype "output"))
    )
    (net (code "129") (name "/IRQ4") (class "Default")
      (node (ref "R384") (pin "2") (pinfunction "2_2") (pintype "passive"))
      (node (ref "U74") (pin "F4") (pinfunction "IRQ4_F4") (pintype "output"))
    )
    (net (code "130") (name "/IRQ5") (class "Default")
      (node (ref "R387") (pin "2") (pinfunction "2_2") (pintype "passive"))
      (node (ref "U74") (pin "F2") (pinfunction "IRQ5_F2") (pintype "output"))
    )
    (net (code "131") (name "/IRQ7") (class "Default")
      (node (ref "R389") (pin "2") (pinfunction "2_2") (pintype "passive"))
      (node (ref "U74") (pin "G1") (pinfunction "IRQ7_G1") (pintype "output"))
    )
    (net (code "132") (name "/IRQ9") (class "Default")
      (node (ref "R325") (pin "2") (pinfunction "2_2") (pintype "passive"))
      (node (ref "U74") (pin "N1") (pinfunction "IRQ9_N1") (pintype "output"))
    )
    (net (code "133") (name "/IRQ10") (class "Default")
      (node (ref "R394") (pin "2") (pinfunction "2_2") (pintype "passive"))
      (node (ref "U74") (pin "D5") (pinfunction "IRQ10_D5") (pintype "output"))
    )
    (net (code "134") (name "/IRQ11") (class "Default")
      (node (ref "R396") (pin "2") (pinfunction "2_2") (pintype "passive"))
      (node (ref "U74") (pin "B2") (pinfunction "IRQ11_B2") (pintype "output"))
    )
    (net (code "135") (name "/IRQ14") (class "Default")
      (node (ref "U74") (pin "B4") (pinfunction "IRQ14_B4") (pintype "output"))
    )
    (net (code "136") (name "/IRQ15") (class "Default")
      (node (ref "R391") (pin "2") (pinfunction "2_2") (pintype "passive"))
      (node (ref "U74") (pin "C4") (pinfunction "IRQ15_C4") (pintype "output"))
    )
    (net (code "137") (name "/LA17") (class "Default")
      (node (ref "U74") (pin "A4") (pinfunction "LA17_A4") (pintype "input"))
    )
    (net (code "138") (name "/LA18") (class "Default")
      (node (ref "U74") (pin "C5") (pinfunction "LA18_C5") (pintype "input"))
    )
    (net (code "139") (name "/LA19") (class "Default")
      (node (ref "U74") (pin "A3") (pinfunction "LA19_A3") (pintype "input"))
    )
    (net (code "140") (name "/LA20") (class "Default")
      (node (ref "U74") (pin "E6") (pinfunction "LA20_E6") (pintype "input"))
    )
    (net (code "141") (name "/LA21") (class "Default")
      (node (ref "U74") (pin "A2") (pinfunction "LA21_A2") (pintype "input"))
    )
    (net (code "142") (name "/LA22") (class "Default")
      (node (ref "U74") (pin "A1") (pinfunction "LA22_A1") (pintype "input"))
    )
    (net (code "143") (name "/LA23") (class "Default")
      (node (ref "U74") (pin "E5") (pinfunction "LA23_E5") (pintype "input"))
    )
    (net (code "144") (name "/MEMCS16#") (class "Default")
      (node (ref "R316") (pin "2") (pinfunction "2_2") (pintype "passive"))
      (node (ref "U74") (pin "D3") (pinfunction "MEMCS16#_D3") (pintype "output"))
    )
    (net (code "145") (name "/MEMR#") (class "Default")
      (node (ref "U74") (pin "B5") (pinfunction "MEMR#_B5") (pintype "input"))
    )
    (net (code "146") (name "/MEMW#") (class "Default")
      (node (ref "U74") (pin "D6") (pinfunction "MEMW#_D6") (pintype "input"))
    )
    (net (code "147") (name "/PCMCIA_BALE") (class "Default")
      (node (ref "U74") (pin "D1") (pinfunction "BALE_D1") (pintype "input"))
    )
    (net (code "148") (name "/PCMCIA_CLK") (class "Default")
      (node (ref "R317") (pin "2") (pinfunction "2_2") (pintype "passive"))
    )
    (net (code "149") (name "/PCMCIA_CS") (class "Default")
      (node (ref "R160") (pin "2") (pinfunction "2_2") (pintype "passive"))
      (node (ref "U38") (pin "6") (pinfunction "6_6") (pintype "input"))
    )
    (net (code "150") (name "/PCMCIA_REFRESH") (class "Default")
      (node (ref "U74") (pin "H1") (pinfunction "REFRESH#_H1") (pintype "input"))
    )
    (net (code "151") (name "/PCMCIA_SBHE#") (class "Default")
      (node (ref "U74") (pin "C3") (pinfunction "SBHE#_C3") (pintype "input"))
    )
    (net (code "152") (name "/PCMCIA_Sound") (class "Default")
      (node (ref "U74") (pin "N3") (pinfunction "SPKROUT#_N3") (pintype "output"))
    )
    (net (code "153") (name "/PCMCIA_ZEROWS#") (class "Default")
      (node (ref "U74") (pin "L3") (pinfunction "ZEROWS#_L3") (pintype "output"))
    )
    (net (code "154") (name "/RESET") (class "Default")
      (node (ref "U74") (pin "T3") (pinfunction "RESETDRV_T3") (pintype "input"))
    )
    (net (code "155") (name "/RIOUT#") (class "Default")
      (node (ref "U74") (pin "C8") (pinfunction "RIOUT#_C8") (pintype "output"))
    )
    (net (code "156") (name "/SA0") (class "Default")
      (node (ref "U74") (pin "F5") (pinfunction "SA0_F5") (pintype "input"))
    )
    (net (code "157") (name "/SA1") (class "Default")
      (node (ref "U74") (pin "D4") (pinfunction "SA1_D4") (pintype "input"))
    )
    (net (code "158") (name "/SA2") (class "Default")
      (node (ref "U74") (pin "C2") (pinfunction "SA2_C2") (pintype "input"))
    )
    (net (code "159") (name "/SA3") (class "Default")
      (node (ref "U74") (pin "E4") (pinfunction "SA3_E4") (pintype "input"))
    )
    (net (code "160") (name "/SA4") (class "Default")
      (node (ref "U74") (pin "G5") (pinfunction "SA4_G5") (pintype "input"))
    )
    (net (code "161") (name "/SA5") (class "Default")
      (node (ref "U74") (pin "D2") (pinfunction "SA5_D2") (pintype "input"))
    )
    (net (code "162") (name "/SA6") (class "Default")
      (node (ref "U74") (pin "E3") (pinfunction "SA6_E3") (pintype "input"))
    )
    (net (code "163") (name "/SA7") (class "Default")
      (node (ref "U74") (pin "E2") (pinfunction "SA7_E2") (pintype "input"))
    )
    (net (code "164") (name "/SA8") (class "Default")
      (node (ref "U74") (pin "F1") (pinfunction "SA8_F1") (pintype "input"))
    )
    (net (code "165") (name "/SA9") (class "Default")
      (node (ref "U74") (pin "G4") (pinfunction "SA9_G4") (pintype "input"))
    )
    (net (code "166") (name "/SA10") (class "Default")
      (node (ref "U74") (pin "F3") (pinfunction "SA10_F3") (pintype "input"))
    )
    (net (code "167") (name "/SA11") (class "Default")
      (node (ref "U74") (pin "G2") (pinfunction "SA11_G2") (pintype "input"))
    )
    (net (code "168") (name "/SA12") (class "Default")
      (node (ref "U74") (pin "G3") (pinfunction "SA12_G3") (pintype "input"))
    )
    (net (code "169") (name "/SA13") (class "Default")
      (node (ref "U74") (pin "H2") (pinfunction "SA13_H2") (pintype "input"))
    )
    (net (code "170") (name "/SA14") (class "Default")
      (node (ref "U74") (pin "H4") (pinfunction "SA14_H4") (pintype "input"))
    )
    (net (code "171") (name "/SA15") (class "Default")
      (node (ref "U74") (pin "H3") (pinfunction "SA15_H3") (pintype "input"))
    )
    (net (code "173") (name "/SD0") (class "Default")
      (node (ref "U74") (pin "K2") (pinfunction "SD0_K2") (pintype "bidirectional"))
    )
    (net (code "174") (name "/SD1") (class "Default")
      (node (ref "U74") (pin "L1") (pinfunction "SD1_L1") (pintype "bidirectional"))
    )
    (net (code "175") (name "/SD2") (class "Default")
      (node (ref "U74") (pin "L2") (pinfunction "SD2_L2") (pintype "bidirectional"))
    )
    (net (code "176") (name "/SD3") (class "Default")
      (node (ref "U74") (pin "M1") (pinfunction "SD3_M1") (pintype "bidirectional"))
    )
    (net (code "177") (name "/SD4") (class "Default")
      (node (ref "U74") (pin "L4") (pinfunction "SD4_L4") (pintype "bidirectional"))
    )
    (net (code "178") (name "/SD5") (class "Default")
      (node (ref "U74") (pin "M2") (pinfunction "SD5_M2") (pintype "bidirectional"))
    )
    (net (code "179") (name "/SD6") (class "Default")
      (node (ref "U74") (pin "M3") (pinfunction "SD6_M3") (pintype "bidirectional"))
    )
    (net (code "180") (name "/SD7") (class "Default")
      (node (ref "U74") (pin "N2") (pinfunction "SD7_N2") (pintype "bidirectional"))
    )
    (net (code "181") (name "/SD8") (class "Default")
      (node (ref "U74") (pin "A5") (pinfunction "SD8_A5") (pintype "bidirectional"))
    )
    (net (code "182") (name "/SD9") (class "Default")
      (node (ref "U74") (pin "B6") (pinfunction "SD9_B6") (pintype "bidirectional"))
    )
    (net (code "183") (name "/SD10") (class "Default")
      (node (ref "U74") (pin "C6") (pinfunction "SD10_C6") (pintype "bidirectional"))
    )
    (net (code "184") (name "/SD11") (class "Default")
      (node (ref "U74") (pin "A6") (pinfunction "SD11_A6") (pintype "bidirectional"))
    )
    (net (code "185") (name "/SD12") (class "Default")
      (node (ref "U74") (pin "B7") (pinfunction "SD12_B7") (pintype "bidirectional"))
    )
    (net (code "186") (name "/SD13") (class "Default")
      (node (ref "U74") (pin "C7") (pinfunction "SD13_C7") (pintype "bidirectional"))
    )
    (net (code "187") (name "/SD14") (class "Default")
      (node (ref "U74") (pin "A7") (pinfunction "SD14_A7") (pintype "bidirectional"))
    )
    (net (code "188") (name "/SD15") (class "Default")
      (node (ref "U74") (pin "B8") (pinfunction "SD15_B8") (pintype "bidirectional"))
    )
    (net (code "190") (name "GND") (class "Default")
      (node (ref "C114") (pin "1") (pinfunction "1_1") (pintype "passive"))
      (node (ref "C115") (pin "1") (pinfunction "1_1") (pintype "passive"))
      (node (ref "C116") (pin "2") (pinfunction "2_2") (pintype "passive"))
      (node (ref "C119") (pin "2") (pinfunction "2_2") (pintype "passive"))
      (node (ref "C122") (pin "2") (pinfunction "2_2") (pintype "passive"))
      (node (ref "C124") (pin "1") (pinfunction "+_1") (pintype "passive"))
      (node (ref "C126") (pin "2") (pinfunction "-_2") (pintype "passive"))
      (node (ref "C273") (pin "2") (pinfunction "-_2") (pintype "passive"))
      (node (ref "C276") (pin "2") (pinfunction "2_2") (pintype "passive"))
      (node (ref "C278") (pin "1") (pinfunction "+_1") (pintype "passive"))
      (node (ref "C279") (pin "2") (pinfunction "-_2") (pintype "passive"))
      (node (ref "C87") (pin "2") (pinfunction "-_2") (pintype "passive"))
      (node (ref "J10") (pin "1") (pinfunction "GND_1") (pintype "power_in"))
      (node (ref "J10") (pin "138") (pinfunction "GND_138") (pintype "power_in"))
      (node (ref "J10") (pin "139") (pinfunction "GND_139") (pintype "power_in"))
      (node (ref "J10") (pin "140") (pinfunction "GND_140") (pintype "power_in"))
      (node (ref "J10") (pin "2") (pinfunction "GND_2") (pintype "power_in"))
      (node (ref "J10") (pin "3") (pinfunction "GND_3") (pintype "power_in"))
      (node (ref "J10") (pin "68") (pinfunction "GND_68") (pintype "power_in"))
      (node (ref "J10") (pin "69") (pinfunction "GND_69") (pintype "power_in"))
      (node (ref "J10") (pin "70") (pinfunction "GND_70") (pintype "power_in"))
      (node (ref "J10") (pin "71") (pinfunction "GND_71") (pintype "power_in"))
      (node (ref "J10") (pin "72") (pinfunction "GND_72") (pintype "power_in"))
      (node (ref "J10") (pin "73") (pinfunction "GND_73") (pintype "power_in"))
      (node (ref "R126") (pin "2") (pinfunction "2_2") (pintype "passive"))
      (node (ref "R160") (pin "1") (pinfunction "1_1") (pintype "passive"))
      (node (ref "R379") (pin "1") (pinfunction "1_1") (pintype "passive"))
      (node (ref "U70") (pin "12") (pinfunction "GND_12") (pintype "power_in"))
      (node (ref "U74") (pin "D7") (pinfunction "GND_D7") (pintype "power_in"))
      (node (ref "U74") (pin "E11") (pinfunction "GND_E11") (pintype "power_in"))
      (node (ref "U74") (pin "E7") (pinfunction "GND_E7") (pintype "power_in"))
      (node (ref "U74") (pin "E8") (pinfunction "GND_E8") (pintype "power_in"))
      (node (ref "U74") (pin "E9") (pinfunction "GND_E9") (pintype "power_in"))
      (node (ref "U74") (pin "F10") (pinfunction "GND_F10") (pintype "power_in"))
      (node (ref "U74") (pin "F11") (pinfunction "GND_F11") (pintype "power_in"))
      (node (ref "U74") (pin "F6") (pinfunction "GND_F6") (pintype "power_in"))
      (node (ref "U74") (pin "F7") (pinfunction "GND_F7") (pintype "power_in"))
      (node (ref "U74") (pin "F8") (pinfunction "GND_F8") (pintype "power_in"))
      (node (ref "U74") (pin "F9") (pinfunction "GND_F9") (pintype "power_in"))
      (node (ref "U74") (pin "G10") (pinfunction "GND_G10") (pintype "power_in"))
      (node (ref "U74") (pin "G11") (pinfunction "GND_G11") (pintype "power_in"))
      (node (ref "U74") (pin "G12") (pinfunction "GND_G12") (pintype "power_in"))
      (node (ref "U74") (pin "G6") (pinfunction "GND_G6") (pintype "power_in"))
      (node (ref "U74") (pin "G7") (pinfunction "GND_G7") (pintype "power_in"))
      (node (ref "U74") (pin "G8") (pinfunction "GND_G8") (pintype "power_in"))
      (node (ref "U74") (pin "G9") (pinfunction "GND_G9") (pintype "power_in"))
      (node (ref "U74") (pin "H10") (pinfunction "GND_H10") (pintype "power_in"))
      (node (ref "U74") (pin "H11") (pinfunction "GND_H11") (pintype "power_in"))
      (node (ref "U74") (pin "H12") (pinfunction "GND_H12") (pintype "power_in"))
      (node (ref "U74") (pin "H5") (pinfunction "GND_H5") (pintype "power_in"))
      (node (ref "U74") (pin "H6") (pinfunction "GND_H6") (pintype "power_in"))
      (node (ref "U74") (pin "H7") (pinfunction "GND_H7") (pintype "power_in"))
      (node (ref "U74") (pin "H8") (pinfunction "GND_H8") (pintype "power_in"))
      (node (ref "U74") (pin "H9") (pinfunction "GND_H9") (pintype "power_in"))
      (node (ref "U74") (pin "J10") (pinfunction "GND_J10") (pintype "power_in"))
      (node (ref "U74") (pin "J11") (pinfunction "GND_J11") (pintype "power_in"))
      (node (ref "U74") (pin "J12") (pinfunction "GND_J12") (pintype "power_in"))
      (node (ref "U74") (pin "J13") (pinfunction "GND_J13") (pintype "power_in"))
      (node (ref "U74") (pin "J4") (pinfunction "GND_J4") (pintype "power_in"))
      (node (ref "U74") (pin "J5") (pinfunction "GND_J5") (pintype "power_in"))
      (node (ref "U74") (pin "J6") (pinfunction "GND_J6") (pintype "power_in"))
      (node (ref "U74") (pin "J7") (pinfunction "GND_J7") (pintype "power_in"))
      (node (ref "U74") (pin "J8") (pinfunction "GND_J8") (pintype "power_in"))
      (node (ref "U74") (pin "J9") (pinfunction "GND_J9") (pintype "power_in"))
      (node (ref "U74") (pin "K10") (pinfunction "GND_K10") (pintype "power_in"))
      (node (ref "U74") (pin "K11") (pinfunction "GND_K11") (pintype "power_in"))
      (node (ref "U74") (pin "K12") (pinfunction "GND_K12") (pintype "power_in"))
      (node (ref "U74") (pin "K5") (pinfunction "GND_K5") (pintype "power_in"))
      (node (ref "U74") (pin "K6") (pinfunction "GND_K6") (pintype "power_in"))
      (node (ref "U74") (pin "K7") (pinfunction "GND_K7") (pintype "power_in"))
      (node (ref "U74") (pin "K8") (pinfunction "GND_K8") (pintype "power_in"))
      (node (ref "U74") (pin "K9") (pinfunction "GND_K9") (pintype "power_in"))
      (node (ref "U74") (pin "L10") (pinfunction "GND_L10") (pintype "power_in"))
      (node (ref "U74") (pin "L11") (pinfunction "GND_L11") (pintype "power_in"))
      (node (ref "U74") (pin "L6") (pinfunction "GND_L6") (pintype "power_in"))
      (node (ref "U74") (pin "L7") (pinfunction "GND_L7") (pintype "power_in"))
      (node (ref "U74") (pin "L8") (pinfunction "GND_L8") (pintype "power_in"))
      (node (ref "U74") (pin "L9") (pinfunction "GND_L9") (pintype "power_in"))
      (node (ref "U74") (pin "M10") (pinfunction "GND_M10") (pintype "power_in"))
      (node (ref "U74") (pin "M8") (pinfunction "GND_M8") (pintype "power_in"))
      (node (ref "U74") (pin "M9") (pinfunction "GND_M9") (pintype "power_in"))
      (node (ref "U74") (pin "N9") (pinfunction "GND_N9") (pintype "power_in"))
      (node (ref "U74") (pin "P1") (pinfunction "POWERGOOD_P1") (pintype "input"))
    )
    (net (code "191") (name "Net-(U70-A_VCC3#)") (class "Default")
      (node (ref "U70") (pin "6") (pinfunction "A_VCC3#_6") (pintype "input"))
      (node (ref "U74") (pin "P4") (pinfunction "AVCC3EN#_P4") (pintype "output"))
    )
    (net (code "192") (name "Net-(U70-A_VCC5#)") (class "Default")
      (node (ref "U70") (pin "5") (pinfunction "A_VCC5#_5") (pintype "input"))
      (node (ref "U74") (pin "M6") (pinfunction "AVCC5EN#_M6") (pintype "output"))
    )
    (net (code "193") (name "Net-(U70-A_VPP_PGM)") (class "Default")
      (node (ref "U70") (pin "3") (pinfunction "A_VPP_PGM_3") (pintype "input"))
      (node (ref "U74") (pin "M5") (pinfunction "AVPP_EN1_M5") (pintype "output"))
    )
    (net (code "194") (name "Net-(U70-A_VPP_VCC)") (class "Default")
      (node (ref "U70") (pin "4") (pinfunction "A_VPP_VCC_4") (pintype "input"))
      (node (ref "U74") (pin "T2") (pinfunction "AVPP_EN0_T2") (pintype "output"))
    )
    (net (code "195") (name "Net-(U70-B_VCC3#)") (class "Default")
      (node (ref "U70") (pin "26") (pinfunction "B_VCC3#_26") (pintype "input"))
      (node (ref "U74") (pin "R2") (pinfunction "BVCC3EN#_R2") (pintype "output"))
    )
    (net (code "196") (name "Net-(U70-B_VCC5#)") (class "Default")
      (node (ref "U70") (pin "27") (pinfunction "B_VCC5#_27") (pintype "input"))
      (node (ref "U74") (pin "T1") (pinfunction "BVCC5EN#_T1") (pintype "output"))
    )
    (net (code "197") (name "Net-(U70-B_VPP_PGM)") (class "Default")
      (node (ref "U70") (pin "29") (pinfunction "B_VPP_PGM_29") (pintype "input"))
      (node (ref "U74") (pin "P2") (pinfunction "BVPP_EN1_P2") (pintype "output"))
    )
    (net (code "198") (name "Net-(U70-B_VPP_VCC)") (class "Default")
      (node (ref "U70") (pin "28") (pinfunction "B_VPP_VCC_28") (pintype "input"))
      (node (ref "U74") (pin "R1") (pinfunction "BVPP_EN0_R1") (pintype "output"))
    )
    (net (code "199") (name "Net-(U70-SHDN#)") (class "Default")
      (node (ref "R363") (pin "1") (pinfunction "1_1") (pintype "passive"))
      (node (ref "U70") (pin "14") (pinfunction "SHDN#_14") (pintype "output"))
    )
    (net (code "200") (name "Net-(U74-CS#)") (class "Default")
      (node (ref "U38") (pin "2") (pinfunction "2_2") (pintype "output"))
      (node (ref "U74") (pin "M4") (pinfunction "CS#_M4") (pintype "input"))
    )
    (net (code "201") (name "Net-(U74-INTR#)") (class "Default")
      (node (ref "R162") (pin "1") (pinfunction "1_1") (pintype "passive"))
      (node (ref "U74") (pin "L5") (pinfunction "INTR#_L5") (pintype "output"))
    )
    (net (code "202") (name "Net-(U74-SYSCLK)") (class "Default")
      (node (ref "R317") (pin "1") (pinfunction "1_1") (pintype "passive"))
      (node (ref "U74") (pin "C1") (pinfunction "SYSCLK_C1") (pintype "input"))
    )
    (net (code "203") (name "PNET1") (class "Default")
      (node (ref "C114") (pin "2") (pinfunction "2_2") (pintype "passive"))
      (node (ref "C115") (pin "2") (pinfunction "2_2") (pintype "passive"))
      (node (ref "C122") (pin "1") (pinfunction "1_1") (pintype "passive"))
      (node (ref "R117") (pin "1") (pinfunction "1_1") (pintype "passive"))
      (node (ref "R162") (pin "2") (pinfunction "2_2") (pintype "passive"))
      (node (ref "R165") (pin "2") (pinfunction "2_2") (pintype "passive"))
      (node (ref "R177") (pin "1") (pinfunction "1_1") (pintype "passive"))
      (node (ref "R312") (pin "1") (pinfunction "1_1") (pintype "passive"))
      (node (ref "U70") (pin "15") (pinfunction "3V_15") (pintype "power_in"))
      (node (ref "U70") (pin "16") (pinfunction "3V_16") (pintype "power_in"))
      (node (ref "U70") (pin "17") (pinfunction "3V_17") (pintype "power_in"))
      (node (ref "U74") (pin "D8") (pinfunction "VCCAT_D8") (pintype "power_in"))
      (node (ref "U74") (pin "K4") (pinfunction "VCCAT_K4") (pintype "power_in"))
      (node (ref "U74") (pin "N8") (pinfunction "VCC_N8") (pintype "power_in"))
    )
    (net (code "204") (name "PNET5") (class "Default")
      (node (ref "C276") (pin "1") (pinfunction "1_1") (pintype "passive"))
      (node (ref "R363") (pin "2") (pinfunction "2_2") (pintype "passive"))
      (node (ref "U70") (pin "1") (pinfunction "5V_1") (pintype "power_in"))
      (node (ref "U70") (pin "2") (pinfunction "5V_2") (pintype "power_in"))
      (node (ref "U70") (pin "25") (pinfunction "VDD_25") (pintype "power_in"))
      (node (ref "U70") (pin "30") (pinfunction "5V_30") (pintype "power_in"))
    )
    (net (code "205") (name "PNET7") (class "Default")
      (node (ref "R115") (pin "1") (pinfunction "1_1") (pintype "passive"))
      (node (ref "R316") (pin "1") (pinfunction "1_1") (pintype "passive"))
      (node (ref "R325") (pin "1") (pinfunction "1_1") (pintype "passive"))
      (node (ref "R384") (pin "1") (pinfunction "1_1") (pintype "passive"))
      (node (ref "R387") (pin "1") (pinfunction "1_1") (pintype "passive"))
      (node (ref "R389") (pin "1") (pinfunction "1_1") (pintype "passive"))
      (node (ref "R391") (pin "1") (pinfunction "1_1") (pintype "passive"))
      (node (ref "R394") (pin "1") (pinfunction "1_1") (pintype "passive"))
      (node (ref "R396") (pin "1") (pinfunction "1_1") (pintype "passive"))
    )
    (net (code "206") (name "PNET9") (class "Default")
      (node (ref "C116") (pin "1") (pinfunction "1_1") (pintype "passive"))
      (node (ref "C278") (pin "2") (pinfunction "-_2") (pintype "passive"))
      (node (ref "C279") (pin "1") (pinfunction "+_1") (pintype "passive"))
      (node (ref "J10") (pin "104") (pinfunction "VCC_104") (pintype "power_in"))
      (node (ref "J10") (pin "105") (pinfunction "VCC_105") (pintype "power_in"))
      (node (ref "R166") (pin "1") (pinfunction "1_1") (pintype "passive"))
      (node (ref "R169") (pin "1") (pinfunction "1_1") (pintype "passive"))
      (node (ref "R170") (pin "1") (pinfunction "1_1") (pintype "passive"))
      (node (ref "R172") (pin "2") (pinfunction "2_2") (pintype "passive"))
      (node (ref "R175") (pin "2") (pinfunction "2_2") (pintype "passive"))
      (node (ref "R178") (pin "2") (pinfunction "2_2") (pintype "passive"))
      (node (ref "R379") (pin "2") (pinfunction "2_2") (pintype "passive"))
      (node (ref "U70") (pin "20") (pinfunction "BVCC_20") (pintype "power_in"))
      (node (ref "U74") (pin "E10") (pinfunction "VCCSLOT#1_E10") (pintype "power_in"))
      (node (ref "U74") (pin "H13") (pinfunction "VCCSLOT#1_H13") (pintype "power_in"))
    )
    (net (code "207") (name "PNET10") (class "Default")
      (node (ref "C119") (pin "1") (pinfunction "1_1") (pintype "passive"))
      (node (ref "C126") (pin "1") (pinfunction "+_1") (pintype "passive"))
      (node (ref "C87") (pin "1") (pinfunction "+_1") (pintype "passive"))
      (node (ref "J10") (pin "34") (pinfunction "VCC_34") (pintype "power_in"))
      (node (ref "J10") (pin "35") (pinfunction "VCC_35") (pintype "power_in"))
      (node (ref "R126") (pin "1") (pinfunction "1_1") (pintype "passive"))
      (node (ref "R163") (pin "1") (pinfunction "1_1") (pintype "passive"))
      (node (ref "R164") (pin "1") (pinfunction "1_1") (pintype "passive"))
      (node (ref "R168") (pin "1") (pinfunction "1_1") (pintype "passive"))
      (node (ref "R174") (pin "1") (pinfunction "1_1") (pintype "passive"))
      (node (ref "R176") (pin "1") (pinfunction "1_1") (pintype "passive"))
      (node (ref "R179") (pin "1") (pinfunction "1_1") (pintype "passive"))
      (node (ref "U70") (pin "10") (pinfunction "AVCC_10") (pintype "power_in"))
      (node (ref "U74") (pin "N12") (pinfunction "VCCSLOT#0_N12") (pintype "power_in"))
      (node (ref "U74") (pin "N7") (pinfunction "VCCSLOT#0_N7") (pintype "power_in"))
    )
    (net (code "208") (name "unconnected-(J10-NC-Pad47)") (class "Default")
      (node (ref "J10") (pin "47") (pinfunction "NC_47") (pintype "bidirectional+no_connect"))
    )
    (net (code "209") (name "unconnected-(J10-NC-Pad117)") (class "Default")
      (node (ref "J10") (pin "117") (pinfunction "NC_117") (pintype "bidirectional+no_connect"))
    )
    (net (code "210") (name "unconnected-(U70-APWR_GOOD#-Pad13)") (class "Default")
      (node (ref "U70") (pin "13") (pinfunction "APWR_GOOD#_13") (pintype "output+no_connect"))
    )
    (net (code "211") (name "unconnected-(U70-AVCC-Pad9)") (class "Default")
      (node (ref "U70") (pin "9") (pinfunction "AVCC_9") (pintype "power_in+no_connect"))
    )
    (net (code "212") (name "unconnected-(U70-AVCC-Pad11)") (class "Default")
      (node (ref "U70") (pin "11") (pinfunction "AVCC_11") (pintype "power_in+no_connect"))
    )
    (net (code "213") (name "unconnected-(U70-BPWR_GOOD#-Pad19)") (class "Default")
      (node (ref "U70") (pin "19") (pinfunction "BPWR_GOOD#_19") (pintype "output+no_connect"))
    )
    (net (code "214") (name "unconnected-(U70-BVCC-Pad21)") (class "Default")
      (node (ref "U70") (pin "21") (pinfunction "BVCC_21") (pintype "power_in+no_connect"))
    )
    (net (code "215") (name "unconnected-(U70-BVCC-Pad22)") (class "Default")
      (node (ref "U70") (pin "22") (pinfunction "BVCC_22") (pintype "power_in+no_connect"))
    )
    (net (code "216") (name "unconnected-(U70-OC#-Pad18)") (class "Default")
      (node (ref "U70") (pin "18") (pinfunction "OC#_18") (pintype "output+no_connect"))
    )
    (net (code "217") (name "unconnected-(U74-IRQ12-PadB3)") (class "Default")
      (node (ref "U74") (pin "B3") (pinfunction "IRQ12_B3") (pintype "output+no_connect"))
    )
  )
)
